# avr_g1000l_24.net
KiCad netlist of a schematic drawn in EAGLE
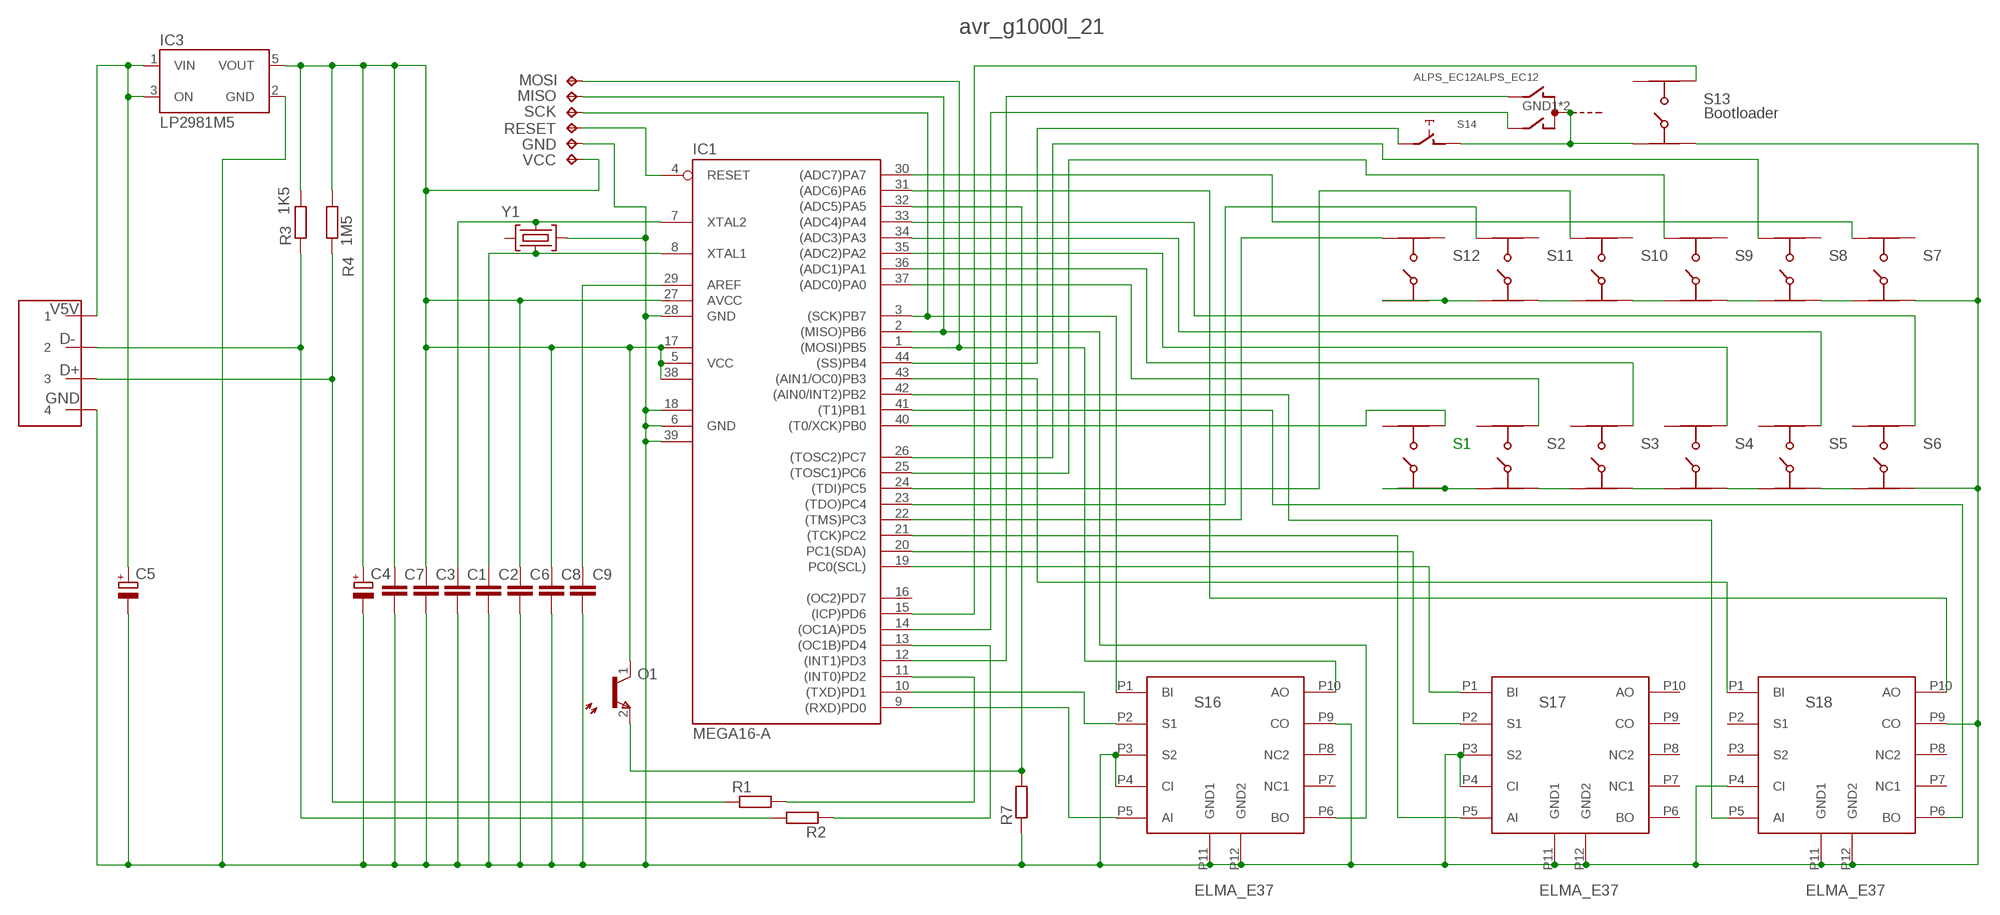
[diagram p0: schematic, sheet 1]

(export (version "E")
  (design (tool "Eeschema 10.0.6"))
  (components
    (comp (ref "C1")
      (value "C-EUC0402")
      (footprint "eagle-import:C0402")
      (libsource (lib "eagle-import") (part "C-EUC0402"))
    )
    (comp (ref "C2")
      (value "C-EUC0402")
      (footprint "eagle-import:C0402")
      (libsource (lib "eagle-import") (part "C-EUC0402"))
    )
    (comp (ref "C3")
      (value "C-EUC0402")
      (footprint "eagle-import:C0402")
      (libsource (lib "eagle-import") (part "C-EUC0402"))
    )
    (comp (ref "C4")
      (value "CPOL-EUSMCA")
      (footprint "eagle-import:SMC_A")
      (libsource (lib "eagle-import") (part "CPOL-EUSMCA"))
    )
    (comp (ref "C5")
      (value "CPOL-EUSMCA")
      (footprint "eagle-import:SMC_A")
      (libsource (lib "eagle-import") (part "CPOL-EUSMCA"))
    )
    (comp (ref "C6")
      (value "C-EUC0402")
      (footprint "eagle-import:C0402")
      (libsource (lib "eagle-import") (part "C-EUC0402"))
    )
    (comp (ref "C7")
      (value "C-EUC0402")
      (footprint "eagle-import:C0402")
      (libsource (lib "eagle-import") (part "C-EUC0402"))
    )
    (comp (ref "C8")
      (value "C-EUC0402")
      (footprint "eagle-import:C0402")
      (libsource (lib "eagle-import") (part "C-EUC0402"))
    )
    (comp (ref "C9")
      (value "C-EUC0402")
      (footprint "eagle-import:C0402")
      (libsource (lib "eagle-import") (part "C-EUC0402"))
    )
    (comp (ref "GND")
      (value "TPTP10R")
      (footprint "eagle-import:TP10R")
      (libsource (lib "eagle-import") (part "TPTP10R"))
    )
    (comp (ref "IC1")
      (value "MEGA16-A")
      (footprint "eagle-import:TQFP44")
      (fields (field (name "MPN") "ATMEGA16-16AU"))
      (libsource (lib "eagle-import") (part "MEGA16-A"))
    )
    (comp (ref "IC3")
      (value "LP2981M5")
      (footprint "eagle-import:SOT23-5")
      (libsource (lib "eagle-import") (part "LP2981M5"))
    )
    (comp (ref "MISO")
      (value "TPTP10R")
      (footprint "eagle-import:TP10R")
      (libsource (lib "eagle-import") (part "TPTP10R"))
    )
    (comp (ref "MOSI")
      (value "TPTP10R")
      (footprint "eagle-import:TP10R")
      (libsource (lib "eagle-import") (part "TPTP10R"))
    )
    (comp (ref "O1")
      (value "KPS-3227KPS-3227")
      (footprint "eagle-import:RESC3216X110")
      (libsource (lib "eagle-import") (part "KPS-3227KPS-3227"))
    )
    (comp (ref "R1")
      (value "R-EU_R0603")
      (footprint "eagle-import:R0603")
      (libsource (lib "eagle-import") (part "R-EU_R0603"))
    )
    (comp (ref "R2")
      (value "R-EU_R0603")
      (footprint "eagle-import:R0603")
      (libsource (lib "eagle-import") (part "R-EU_R0603"))
    )
    (comp (ref "R3")
      (value "1K5")
      (footprint "eagle-import:R0603")
      (libsource (lib "eagle-import") (part "R-EU_R0603"))
    )
    (comp (ref "R4")
      (value "1M5")
      (footprint "eagle-import:R0603")
      (libsource (lib "eagle-import") (part "R-EU_R0603"))
    )
    (comp (ref "R7")
      (value "R-EU_R0603")
      (footprint "eagle-import:R0603")
      (libsource (lib "eagle-import") (part "R-EU_R0603"))
    )
    (comp (ref "RESET")
      (value "TPTP10R")
      (footprint "eagle-import:TP10R")
      (libsource (lib "eagle-import") (part "TPTP10R"))
    )
    (comp (ref "S1")
      (value "B3FS1000")
      (footprint "eagle-import:B3FS1000")
      (fields (field (name "SPICEPREFIX") "S"))
      (libsource (lib "eagle-import") (part "B3FS1000"))
    )
    (comp (ref "S2")
      (value "B3FS1000")
      (footprint "eagle-import:B3FS1000")
      (libsource (lib "eagle-import") (part "omron b3fs1000_11028112_B3FS1000"))
    )
    (comp (ref "S3")
      (value "B3FS1000")
      (footprint "eagle-import:B3FS1000")
      (libsource (lib "eagle-import") (part "omron b3fs1000_11028112_B3FS1000"))
    )
    (comp (ref "S4")
      (value "B3FS1000")
      (footprint "eagle-import:B3FS1000")
      (libsource (lib "eagle-import") (part "omron b3fs1000_11028112_B3FS1000"))
    )
    (comp (ref "S5")
      (value "B3FS1000")
      (footprint "eagle-import:B3FS1000")
      (libsource (lib "eagle-import") (part "omron b3fs1000_11028112_B3FS1000"))
    )
    (comp (ref "S6")
      (value "B3FS1000")
      (footprint "eagle-import:B3FS1000")
      (libsource (lib "eagle-import") (part "omron b3fs1000_11028112_B3FS1000"))
    )
    (comp (ref "S7")
      (value "B3FS1000")
      (footprint "eagle-import:B3FS1000")
      (libsource (lib "eagle-import") (part "omron b3fs1000_11028112_B3FS1000"))
    )
    (comp (ref "S8")
      (value "B3FS1000")
      (footprint "eagle-import:B3FS1000")
      (libsource (lib "eagle-import") (part "omron b3fs1000_11028112_B3FS1000"))
    )
    (comp (ref "S9")
      (value "B3FS1000")
      (footprint "eagle-import:B3FS1000")
      (libsource (lib "eagle-import") (part "omron b3fs1000_11028112_B3FS1000"))
    )
    (comp (ref "S10")
      (value "B3FS1000")
      (footprint "eagle-import:B3FS1000")
      (libsource (lib "eagle-import") (part "omron b3fs1000_11028112_B3FS1000"))
    )
    (comp (ref "S11")
      (value "B3FS1000")
      (footprint "eagle-import:B3FS1000")
      (libsource (lib "eagle-import") (part "omron b3fs1000_11028112_B3FS1000"))
    )
    (comp (ref "S12")
      (value "B3FS1000")
      (footprint "eagle-import:B3FS1000")
      (libsource (lib "eagle-import") (part "omron b3fs1000_11028112_B3FS1000"))
    )
    (comp (ref "S13")
      (value "B3FS1000")
      (footprint "eagle-import:B3FS1000")
      (libsource (lib "eagle-import") (part "omron b3fs1000_11028112_B3FS1000"))
    )
    (comp (ref "S14")
      (value "ALPS_EC12ALPS_EC12")
      (footprint "eagle-import:ALPS_EC12E_SW")
      (libsource (lib "eagle-import") (part "ALPS_EC12ALPS_EC12"))
    )
    (comp (ref "S16")
      (value "ELMA_E37")
      (footprint "eagle-import:ELMA_E37")
      (libsource (lib "eagle-import") (part "ELMA_E37"))
    )
    (comp (ref "S17")
      (value "ELMA_E37")
      (footprint "eagle-import:ELMA_E37")
      (libsource (lib "eagle-import") (part "ELMA_E37"))
    )
    (comp (ref "S18")
      (value "ELMA_E37")
      (footprint "eagle-import:ELMA_E37")
      (libsource (lib "eagle-import") (part "ELMA_E37"))
    )
    (comp (ref "SCK")
      (value "TPTP10R")
      (footprint "eagle-import:TP10R")
      (libsource (lib "eagle-import") (part "TPTP10R"))
    )
    (comp (ref "U$4")
      (value "HEADER4X1.27")
      (footprint "eagle-import:HEADER4X1.27")
      (libsource (lib "eagle-import") (part "HEADER4X1.27"))
    )
    (comp (ref "VCC")
      (value "TPTP10R")
      (footprint "eagle-import:TP10R")
      (libsource (lib "eagle-import") (part "TPTP10R"))
    )
    (comp (ref "Y1")
      (value "MJ-CRYSTALMJ")
      (footprint "eagle-import:OSCCC500X320X100")
      (libsource (lib "eagle-import") (part "MJ-CRYSTALMJ"))
    )
  )
  (nets
    (net (code "1") (name "/D+") (class "Default")
      (node (ref "R2") (pin "2") (pinfunction "2_2") (pintype "passive"))
      (node (ref "R3") (pin "1") (pinfunction "1_1") (pintype "passive"))
      (node (ref "U$4") (pin "P2") (pinfunction "2_P2") (pintype "bidirectional"))
    )
    (net (code "2") (name "/D-") (class "Default")
      (node (ref "R1") (pin "1") (pinfunction "1_1") (pintype "passive"))
      (node (ref "R4") (pin "1") (pinfunction "1_1") (pintype "passive"))
      (node (ref "U$4") (pin "P3") (pinfunction "3_P3") (pintype "bidirectional"))
    )
    (net (code "3") (name "/GND") (class "Default")
      (node (ref "C1") (pin "2") (pinfunction "2_2") (pintype "passive"))
      (node (ref "C2") (pin "2") (pinfunction "2_2") (pintype "passive"))
      (node (ref "C3") (pin "2") (pinfunction "2_2") (pintype "passive"))
      (node (ref "C4") (pin "-") (pinfunction "-_-") (pintype "passive"))
      (node (ref "C5") (pin "-") (pinfunction "-_-") (pintype "passive"))
      (node (ref "C6") (pin "2") (pinfunction "2_2") (pintype "passive"))
      (node (ref "C7") (pin "2") (pinfunction "2_2") (pintype "passive"))
      (node (ref "C8") (pin "2") (pinfunction "2_2") (pintype "passive"))
      (node (ref "C9") (pin "2") (pinfunction "2_2") (pintype "passive"))
      (node (ref "GND") (pin "TP") (pinfunction "TP_TP") (pintype "input"))
      (node (ref "IC1") (pin "18") (pinfunction "GND1_18") (pintype "power_in"))
      (node (ref "IC1") (pin "28") (pinfunction "GND_28") (pintype "power_in"))
      (node (ref "IC1") (pin "39") (pinfunction "GND2_39") (pintype "power_in"))
      (node (ref "IC1") (pin "6") (pinfunction "GND_6") (pintype "power_in"))
      (node (ref "IC3") (pin "2") (pinfunction "GND_2") (pintype "power_in"))
      (node (ref "R7") (pin "1") (pinfunction "1_1") (pintype "passive"))
      (node (ref "S1") (pin "3") (pinfunction "3_3") (pintype "passive"))
      (node (ref "S1") (pin "4") (pinfunction "4_4") (pintype "passive"))
      (node (ref "S10") (pin "3") (pinfunction "3_3") (pintype "passive"))
      (node (ref "S10") (pin "4") (pinfunction "4_4") (pintype "passive"))
      (node (ref "S11") (pin "3") (pinfunction "3_3") (pintype "passive"))
      (node (ref "S11") (pin "4") (pinfunction "4_4") (pintype "passive"))
      (node (ref "S12") (pin "3") (pinfunction "3_3") (pintype "passive"))
      (node (ref "S12") (pin "4") (pinfunction "4_4") (pintype "passive"))
      (node (ref "S13") (pin "3") (pinfunction "3_3") (pintype "passive"))
      (node (ref "S13") (pin "4") (pinfunction "4_4") (pintype "passive"))
      (node (ref "S14") (pin "C") (pinfunction "C_C") (pintype "passive"))
      (node (ref "S14") (pin "D") (pinfunction "1_D") (pintype "passive"))
      (node (ref "S14") (pin "GND1") (pinfunction "G_GND1") (pintype "passive"))
      (node (ref "S14") (pin "GND2") (pinfunction "G_GND2") (pintype "passive"))
      (node (ref "S16") (pin "P11") (pinfunction "GND1_P11") (pintype "bidirectional"))
      (node (ref "S16") (pin "P12") (pinfunction "GND2_P12") (pintype "bidirectional"))
      (node (ref "S16") (pin "P3") (pinfunction "S2_P3") (pintype "bidirectional"))
      (node (ref "S16") (pin "P4") (pinfunction "CI_P4") (pintype "bidirectional"))
      (node (ref "S16") (pin "P9") (pinfunction "CO_P9") (pintype "bidirectional"))
      (node (ref "S17") (pin "P11") (pinfunction "GND1_P11") (pintype "bidirectional"))
      (node (ref "S17") (pin "P12") (pinfunction "GND2_P12") (pintype "bidirectional"))
      (node (ref "S17") (pin "P3") (pinfunction "S2_P3") (pintype "bidirectional"))
      (node (ref "S17") (pin "P4") (pinfunction "CI_P4") (pintype "bidirectional"))
      (node (ref "S18") (pin "P11") (pinfunction "GND1_P11") (pintype "bidirectional"))
      (node (ref "S18") (pin "P12") (pinfunction "GND2_P12") (pintype "bidirectional"))
      (node (ref "S18") (pin "P4") (pinfunction "CI_P4") (pintype "bidirectional"))
      (node (ref "S18") (pin "P9") (pinfunction "CO_P9") (pintype "bidirectional"))
      (node (ref "S2") (pin "3") (pinfunction "3_3") (pintype "passive"))
      (node (ref "S2") (pin "4") (pinfunction "4_4") (pintype "passive"))
      (node (ref "S3") (pin "3") (pinfunction "3_3") (pintype "passive"))
      (node (ref "S3") (pin "4") (pinfunction "4_4") (pintype "passive"))
      (node (ref "S4") (pin "3") (pinfunction "3_3") (pintype "passive"))
      (node (ref "S4") (pin "4") (pinfunction "4_4") (pintype "passive"))
      (node (ref "S5") (pin "3") (pinfunction "3_3") (pintype "passive"))
      (node (ref "S5") (pin "4") (pinfunction "4_4") (pintype "passive"))
      (node (ref "S6") (pin "3") (pinfunction "3_3") (pintype "passive"))
      (node (ref "S6") (pin "4") (pinfunction "4_4") (pintype "passive"))
      (node (ref "S7") (pin "3") (pinfunction "3_3") (pintype "passive"))
      (node (ref "S7") (pin "4") (pinfunction "4_4") (pintype "passive"))
      (node (ref "S8") (pin "3") (pinfunction "3_3") (pintype "passive"))
      (node (ref "S8") (pin "4") (pinfunction "4_4") (pintype "passive"))
      (node (ref "S9") (pin "3") (pinfunction "3_3") (pintype "passive"))
      (node (ref "S9") (pin "4") (pinfunction "4_4") (pintype "passive"))
      (node (ref "U$4") (pin "P4") (pinfunction "4_P4") (pintype "bidirectional"))
      (node (ref "Y1") (pin "2") (pinfunction "GND1_2") (pintype "bidirectional"))
    )
    (net (code "4") (name "/V5V") (class "Default")
      (node (ref "C5") (pin "+") (pinfunction "+_+") (pintype "passive"))
      (node (ref "IC3") (pin "1") (pinfunction "VIN_1") (pintype "power_in"))
      (node (ref "IC3") (pin "3") (pinfunction "ON_3") (pintype "input"))
      (node (ref "U$4") (pin "P1") (pinfunction "1_P1") (pintype "bidirectional"))
    )
    (net (code "5") (name "Net-(IC1-(ADC0)PA0)") (class "Default")
      (node (ref "IC1") (pin "37") (pinfunction "(ADC0)PA0_37") (pintype "bidirectional"))
      (node (ref "S2") (pin "2") (pinfunction "2_2") (pintype "passive"))
    )
    (net (code "6") (name "Net-(IC1-(ADC1)PA1)") (class "Default")
      (node (ref "IC1") (pin "36") (pinfunction "(ADC1)PA1_36") (pintype "bidirectional"))
      (node (ref "S3") (pin "2") (pinfunction "2_2") (pintype "passive"))
    )
    (net (code "7") (name "Net-(IC1-(ADC2)PA2)") (class "Default")
      (node (ref "IC1") (pin "35") (pinfunction "(ADC2)PA2_35") (pintype "bidirectional"))
      (node (ref "S4") (pin "2") (pinfunction "2_2") (pintype "passive"))
    )
    (net (code "8") (name "Net-(IC1-(ADC3)PA3)") (class "Default")
      (node (ref "IC1") (pin "34") (pinfunction "(ADC3)PA3_34") (pintype "bidirectional"))
      (node (ref "S5") (pin "2") (pinfunction "2_2") (pintype "passive"))
    )
    (net (code "9") (name "Net-(IC1-(ADC4)PA4)") (class "Default")
      (node (ref "IC1") (pin "33") (pinfunction "(ADC4)PA4_33") (pintype "bidirectional"))
      (node (ref "S6") (pin "2") (pinfunction "2_2") (pintype "passive"))
    )
    (net (code "10") (name "Net-(IC1-(ADC5)PA5)") (class "Default")
      (node (ref "IC1") (pin "32") (pinfunction "(ADC5)PA5_32") (pintype "bidirectional"))
      (node (ref "O1") (pin "2") (pinfunction "E_2") (pintype "bidirectional"))
      (node (ref "R7") (pin "2") (pinfunction "2_2") (pintype "passive"))
    )
    (net (code "11") (name "Net-(IC1-(ADC6)PA6)") (class "Default")
      (node (ref "IC1") (pin "31") (pinfunction "(ADC6)PA6_31") (pintype "bidirectional"))
      (node (ref "S18") (pin "P10") (pinfunction "AO_P10") (pintype "bidirectional"))
    )
    (net (code "12") (name "Net-(IC1-(ADC7)PA7)") (class "Default")
      (node (ref "IC1") (pin "30") (pinfunction "(ADC7)PA7_30") (pintype "bidirectional"))
      (node (ref "S7") (pin "1") (pinfunction "1_1") (pintype "passive"))
    )
    (net (code "13") (name "Net-(IC1-(AIN0{slash}INT2)PB2)") (class "Default")
      (node (ref "IC1") (pin "42") (pinfunction "(AIN0/INT2)PB2_42") (pintype "bidirectional"))
      (node (ref "S18") (pin "P5") (pinfunction "AI_P5") (pintype "bidirectional"))
    )
    (net (code "14") (name "Net-(IC1-(AIN1{slash}OC0)PB3)") (class "Default")
      (node (ref "IC1") (pin "43") (pinfunction "(AIN1/OC0)PB3_43") (pintype "bidirectional"))
      (node (ref "S18") (pin "P1") (pinfunction "BI_P1") (pintype "bidirectional"))
    )
    (net (code "15") (name "Net-(IC1-(ICP)PD6)") (class "Default")
      (node (ref "IC1") (pin "15") (pinfunction "(ICP)PD6_15") (pintype "bidirectional"))
      (node (ref "S13") (pin "2") (pinfunction "2_2") (pintype "passive"))
    )
    (net (code "16") (name "Net-(IC1-(INT0)PD2)") (class "Default")
      (node (ref "IC1") (pin "11") (pinfunction "(INT0)PD2_11") (pintype "bidirectional"))
      (node (ref "R1") (pin "2") (pinfunction "2_2") (pintype "passive"))
    )
    (net (code "17") (name "Net-(IC1-(INT1)PD3)") (class "Default")
      (node (ref "IC1") (pin "12") (pinfunction "(INT1)PD3_12") (pintype "bidirectional"))
      (node (ref "S14") (pin "B") (pinfunction "B_B") (pintype "passive"))
    )
    (net (code "18") (name "Net-(IC1-(MISO)PB6)") (class "Default")
      (node (ref "IC1") (pin "2") (pinfunction "(MISO)PB6_2") (pintype "bidirectional"))
      (node (ref "MISO") (pin "TP") (pinfunction "TP_TP") (pintype "input"))
      (node (ref "S16") (pin "P6") (pinfunction "BO_P6") (pintype "bidirectional"))
    )
    (net (code "19") (name "Net-(IC1-(MOSI)PB5)") (class "Default")
      (node (ref "IC1") (pin "1") (pinfunction "(MOSI)PB5_1") (pintype "bidirectional"))
      (node (ref "MOSI") (pin "TP") (pinfunction "TP_TP") (pintype "input"))
      (node (ref "S16") (pin "P10") (pinfunction "AO_P10") (pintype "bidirectional"))
    )
    (net (code "20") (name "Net-(IC1-(OC1A)PD5)") (class "Default")
      (node (ref "IC1") (pin "14") (pinfunction "(OC1A)PD5_14") (pintype "bidirectional"))
      (node (ref "S14") (pin "A") (pinfunction "A_A") (pintype "passive"))
    )
    (net (code "21") (name "Net-(IC1-(OC1B)PD4)") (class "Default")
      (node (ref "IC1") (pin "13") (pinfunction "(OC1B)PD4_13") (pintype "bidirectional"))
      (node (ref "R2") (pin "1") (pinfunction "1_1") (pintype "passive"))
    )
    (net (code "22") (name "Net-(IC1-(RXD)PD0)") (class "Default")
      (node (ref "IC1") (pin "9") (pinfunction "(RXD)PD0_9") (pintype "bidirectional"))
      (node (ref "S16") (pin "P5") (pinfunction "AI_P5") (pintype "bidirectional"))
    )
    (net (code "23") (name "Net-(IC1-(SCK)PB7)") (class "Default")
      (node (ref "IC1") (pin "3") (pinfunction "(SCK)PB7_3") (pintype "bidirectional"))
      (node (ref "S16") (pin "P1") (pinfunction "BI_P1") (pintype "bidirectional"))
      (node (ref "SCK") (pin "TP") (pinfunction "TP_TP") (pintype "input"))
    )
    (net (code "24") (name "Net-(IC1-(SS)PB4)") (class "Default")
      (node (ref "IC1") (pin "44") (pinfunction "(SS)PB4_44") (pintype "bidirectional"))
      (node (ref "S14") (pin "E") (pinfunction "2_E") (pintype "passive"))
    )
    (net (code "25") (name "Net-(IC1-(T0{slash}XCK)PB0)") (class "Default")
      (node (ref "IC1") (pin "40") (pinfunction "(T0/XCK)PB0_40") (pintype "bidirectional"))
      (node (ref "S1") (pin "2") (pinfunction "2_2") (pintype "passive"))
    )
    (net (code "26") (name "Net-(IC1-(T1)PB1)") (class "Default")
      (node (ref "IC1") (pin "41") (pinfunction "(T1)PB1_41") (pintype "bidirectional"))
      (node (ref "S18") (pin "P6") (pinfunction "BO_P6") (pintype "bidirectional"))
    )
    (net (code "27") (name "Net-(IC1-(TCK)PC2)") (class "Default")
      (node (ref "IC1") (pin "21") (pinfunction "(TCK)PC2_21") (pintype "bidirectional"))
      (node (ref "S17") (pin "P5") (pinfunction "AI_P5") (pintype "bidirectional"))
    )
    (net (code "28") (name "Net-(IC1-(TDI)PC5)") (class "Default")
      (node (ref "IC1") (pin "24") (pinfunction "(TDI)PC5_24") (pintype "bidirectional"))
      (node (ref "S10") (pin "1") (pinfunction "1_1") (pintype "passive"))
    )
    (net (code "29") (name "Net-(IC1-(TDO)PC4)") (class "Default")
      (node (ref "IC1") (pin "23") (pinfunction "(TDO)PC4_23") (pintype "bidirectional"))
      (node (ref "S11") (pin "1") (pinfunction "1_1") (pintype "passive"))
    )
    (net (code "30") (name "Net-(IC1-(TMS)PC3)") (class "Default")
      (node (ref "IC1") (pin "22") (pinfunction "(TMS)PC3_22") (pintype "bidirectional"))
      (node (ref "S12") (pin "1") (pinfunction "1_1") (pintype "passive"))
    )
    (net (code "31") (name "Net-(IC1-(TOSC1)PC6)") (class "Default")
      (node (ref "IC1") (pin "25") (pinfunction "(TOSC1)PC6_25") (pintype "bidirectional"))
      (node (ref "S9") (pin "1") (pinfunction "1_1") (pintype "passive"))
    )
    (net (code "32") (name "Net-(IC1-(TOSC2)PC7)") (class "Default")
      (node (ref "IC1") (pin "26") (pinfunction "(TOSC2)PC7_26") (pintype "bidirectional"))
      (node (ref "S8") (pin "1") (pinfunction "1_1") (pintype "passive"))
    )
    (net (code "33") (name "Net-(IC1-(TXD)PD1)") (class "Default")
      (node (ref "IC1") (pin "10") (pinfunction "(TXD)PD1_10") (pintype "bidirectional"))
      (node (ref "S16") (pin "P2") (pinfunction "S1_P2") (pintype "bidirectional"))
    )
    (net (code "34") (name "Net-(IC1-AREF)") (class "Default")
      (node (ref "C9") (pin "1") (pinfunction "1_1") (pintype "passive"))
      (node (ref "IC1") (pin "29") (pinfunction "AREF_29") (pintype "passive"))
    )
    (net (code "35") (name "Net-(IC1-AVCC)") (class "Default")
      (node (ref "C3") (pin "1") (pinfunction "1_1") (pintype "passive"))
      (node (ref "C4") (pin "+") (pinfunction "+_+") (pintype "passive"))
      (node (ref "C6") (pin "1") (pinfunction "1_1") (pintype "passive"))
      (node (ref "C7") (pin "1") (pinfunction "1_1") (pintype "passive"))
      (node (ref "C8") (pin "1") (pinfunction "1_1") (pintype "passive"))
      (node (ref "IC1") (pin "17") (pinfunction "VCC1_17") (pintype "power_in"))
      (node (ref "IC1") (pin "27") (pinfunction "AVCC_27") (pintype "power_in"))
      (node (ref "IC1") (pin "38") (pinfunction "VCC2_38") (pintype "power_in"))
      (node (ref "IC1") (pin "5") (pinfunction "VCC_5") (pintype "power_in"))
      (node (ref "IC3") (pin "5") (pinfunction "VOUT_5") (pintype "output"))
      (node (ref "O1") (pin "1") (pinfunction "C_1") (pintype "bidirectional"))
      (node (ref "R3") (pin "2") (pinfunction "2_2") (pintype "passive"))
      (node (ref "R4") (pin "2") (pinfunction "2_2") (pintype "passive"))
      (node (ref "VCC") (pin "TP") (pinfunction "TP_TP") (pintype "input"))
    )
    (net (code "36") (name "Net-(IC1-PC0(SCL))") (class "Default")
      (node (ref "IC1") (pin "19") (pinfunction "PC0(SCL)_19") (pintype "bidirectional"))
      (node (ref "S17") (pin "P1") (pinfunction "BI_P1") (pintype "bidirectional"))
    )
    (net (code "37") (name "Net-(IC1-PC1(SDA))") (class "Default")
      (node (ref "IC1") (pin "20") (pinfunction "PC1(SDA)_20") (pintype "bidirectional"))
      (node (ref "S17") (pin "P2") (pinfunction "S1_P2") (pintype "bidirectional"))
    )
    (net (code "38") (name "Net-(IC1-RESET)") (class "Default")
      (node (ref "IC1") (pin "4") (pinfunction "RESET_4") (pintype "input"))
      (node (ref "RESET") (pin "TP") (pinfunction "TP_TP") (pintype "input"))
    )
    (net (code "39") (name "Net-(IC1-XTAL1)") (class "Default")
      (node (ref "C2") (pin "1") (pinfunction "1_1") (pintype "passive"))
      (node (ref "IC1") (pin "8") (pinfunction "XTAL1_8") (pintype "bidirectional"))
      (node (ref "Y1") (pin "3") (pinfunction "CRYSTAL2_3") (pintype "bidirectional"))
    )
    (net (code "40") (name "Net-(IC1-XTAL2)") (class "Default")
      (node (ref "C1") (pin "1") (pinfunction "1_1") (pintype "passive"))
      (node (ref "IC1") (pin "7") (pinfunction "XTAL2_7") (pintype "bidirectional"))
      (node (ref "Y1") (pin "1") (pinfunction "CRYSTAL1_1") (pintype "bidirectional"))
    )
    (net (code "41") (name "unconnected-(IC1-(OC2)PD7-Pad16)") (class "Default")
      (node (ref "IC1") (pin "16") (pinfunction "(OC2)PD7_16") (pintype "bidirectional"))
    )
    (net (code "42") (name "unconnected-(S1-Pad1)") (class "Default")
      (node (ref "S1") (pin "1") (pinfunction "1_1") (pintype "passive"))
    )
    (net (code "43") (name "unconnected-(S2-Pad1)") (class "Default")
      (node (ref "S2") (pin "1") (pinfunction "1_1") (pintype "passive"))
    )
    (net (code "44") (name "unconnected-(S3-Pad1)") (class "Default")
      (node (ref "S3") (pin "1") (pinfunction "1_1") (pintype "passive"))
    )
    (net (code "45") (name "unconnected-(S4-Pad1)") (class "Default")
      (node (ref "S4") (pin "1") (pinfunction "1_1") (pintype "passive"))
    )
    (net (code "46") (name "unconnected-(S5-Pad1)") (class "Default")
      (node (ref "S5") (pin "1") (pinfunction "1_1") (pintype "passive"))
    )
    (net (code "47") (name "unconnected-(S6-Pad1)") (class "Default")
      (node (ref "S6") (pin "1") (pinfunction "1_1") (pintype "passive"))
    )
    (net (code "48") (name "unconnected-(S7-Pad2)") (class "Default")
      (node (ref "S7") (pin "2") (pinfunction "2_2") (pintype "passive"))
    )
    (net (code "49") (name "unconnected-(S8-Pad2)") (class "Default")
      (node (ref "S8") (pin "2") (pinfunction "2_2") (pintype "passive"))
    )
    (net (code "50") (name "unconnected-(S9-Pad2)") (class "Default")
      (node (ref "S9") (pin "2") (pinfunction "2_2") (pintype "passive"))
    )
    (net (code "51") (name "unconnected-(S10-Pad2)") (class "Default")
      (node (ref "S10") (pin "2") (pinfunction "2_2") (pintype "passive"))
    )
    (net (code "52") (name "unconnected-(S11-Pad2)") (class "Default")
      (node (ref "S11") (pin "2") (pinfunction "2_2") (pintype "passive"))
    )
    (net (code "53") (name "unconnected-(S12-Pad2)") (class "Default")
      (node (ref "S12") (pin "2") (pinfunction "2_2") (pintype "passive"))
    )
    (net (code "54") (name "unconnected-(S13-Pad1)") (class "Default")
      (node (ref "S13") (pin "1") (pinfunction "1_1") (pintype "passive"))
    )
    (net (code "55") (name "unconnected-(S16-NC1-PadP7)") (class "Default")
      (node (ref "S16") (pin "P7") (pinfunction "NC1_P7") (pintype "no_connect"))
    )
    (net (code "56") (name "unconnected-(S16-NC2-PadP8)") (class "Default")
      (node (ref "S16") (pin "P8") (pinfunction "NC2_P8") (pintype "no_connect"))
    )
    (net (code "57") (name "unconnected-(S17-AO-PadP10)") (class "Default")
      (node (ref "S17") (pin "P10") (pinfunction "AO_P10") (pintype "bidirectional"))
    )
    (net (code "58") (name "unconnected-(S17-BO-PadP6)") (class "Default")
      (node (ref "S17") (pin "P6") (pinfunction "BO_P6") (pintype "bidirectional"))
    )
    (net (code "59") (name "unconnected-(S17-CO-PadP9)") (class "Default")
      (node (ref "S17") (pin "P9") (pinfunction "CO_P9") (pintype "bidirectional"))
    )
    (net (code "60") (name "unconnected-(S17-NC1-PadP7)") (class "Default")
      (node (ref "S17") (pin "P7") (pinfunction "NC1_P7") (pintype "no_connect"))
    )
    (net (code "61") (name "unconnected-(S17-NC2-PadP8)") (class "Default")
      (node (ref "S17") (pin "P8") (pinfunction "NC2_P8") (pintype "no_connect"))
    )
    (net (code "62") (name "unconnected-(S18-NC1-PadP7)") (class "Default")
      (node (ref "S18") (pin "P7") (pinfunction "NC1_P7") (pintype "no_connect"))
    )
    (net (code "63") (name "unconnected-(S18-NC2-PadP8)") (class "Default")
      (node (ref "S18") (pin "P8") (pinfunction "NC2_P8") (pintype "no_connect"))
    )
    (net (code "64") (name "unconnected-(S18-S1-PadP2)") (class "Default")
      (node (ref "S18") (pin "P2") (pinfunction "S1_P2") (pintype "bidirectional"))
    )
    (net (code "65") (name "unconnected-(S18-S2-PadP3)") (class "Default")
      (node (ref "S18") (pin "P3") (pinfunction "S2_P3") (pintype "bidirectional"))
    )
    (net (code "66") (name "unconnected-(Y1-GND2-Pad4)") (class "Default")
      (node (ref "Y1") (pin "4") (pinfunction "GND2_4") (pintype "bidirectional"))
    )
  )
)
